# 30to50V-24V_10A.net
KiCad netlist of a schematic drawn in Altium Designer
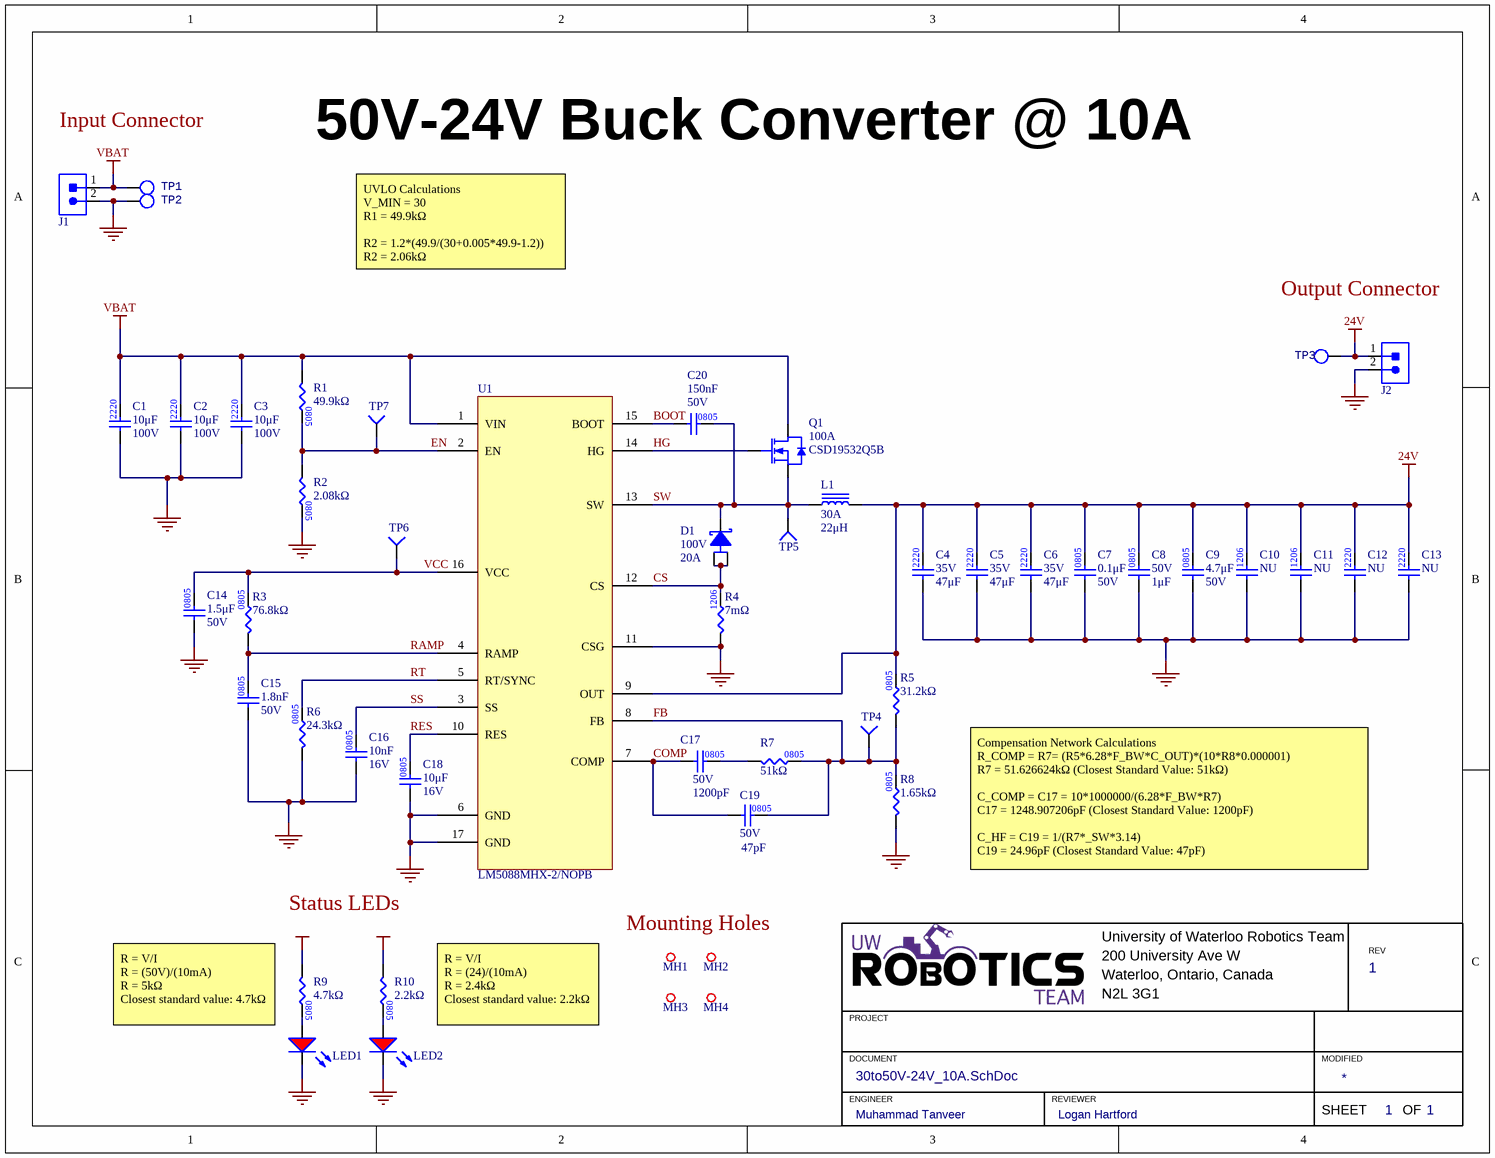
[diagram p0: 30to50V-24V_10A.SchDoc]

(export (version "E")
  (design (tool "Eeschema 10.0.6"))
  (components
    (comp (ref "C1")
      (value "10μF")
      (footprint "CAP2220")
      (description "CAP CER 10UF 100V X7S 2220")
      (fields (field (name "VOLTAGE RATING") "100V") (field (name "Comment") "CAP_10uF_50V_2220"))
      (libsource (lib "UWRT_Schematic_Library_2020") (part "CAP_10uF_50V_2220"))
    )
    (comp (ref "C2")
      (value "10μF")
      (footprint "CAP2220")
      (description "CAP CER 10UF 100V X7S 2220")
      (fields (field (name "VOLTAGE RATING") "100V") (field (name "Comment") "CAP_10uF_50V_2220"))
      (libsource (lib "UWRT_Schematic_Library_2020") (part "CAP_10uF_50V_2220"))
    )
    (comp (ref "C3")
      (value "10μF")
      (footprint "CAP2220")
      (description "CAP CER 10UF 100V X7S 2220")
      (fields (field (name "VOLTAGE RATING") "100V") (field (name "Comment") "CAP_10uF_50V_2220"))
      (libsource (lib "UWRT_Schematic_Library_2020") (part "CAP_10uF_50V_2220"))
    )
    (comp (ref "C4")
      (value "47μF")
      (footprint "CAP2220")
      (description "CAP CER 47UF 35V X7R 2220")
      (fields (field (name "VOLTAGE RATING") "35V") (field (name "Comment") "CAP_47uF_35V_2220"))
      (libsource (lib "UWRT_Schematic_Library_2020") (part "CAP_47uF_35V_2220"))
    )
    (comp (ref "C5")
      (value "47μF")
      (footprint "CAP2220")
      (description "CAP CER 47UF 35V X7R 2220")
      (fields (field (name "VOLTAGE RATING") "35V") (field (name "Comment") "CAP_47uF_35V_2220"))
      (libsource (lib "UWRT_Schematic_Library_2020") (part "CAP_47uF_35V_2220"))
    )
    (comp (ref "C6")
      (value "47μF")
      (footprint "CAP2220")
      (description "CAP CER 47UF 35V X7R 2220")
      (fields (field (name "VOLTAGE RATING") "35V") (field (name "Comment") "CAP_47uF_35V_2220"))
      (libsource (lib "UWRT_Schematic_Library_2020") (part "CAP_47uF_35V_2220"))
    )
    (comp (ref "C7")
      (value "0.1μF")
      (footprint "CAP0805")
      (description "CAP CER 0.1UF 50V X7R 0805")
      (fields
        (field (name "LCSC PART #") "C49678")
        (field (name "VOLTAGE RATING") "50V")
        (field (name "Comment") "CAP_0.1uF_50V_0805")
      )
      (libsource (lib "UWRT_Schematic_Library_2020") (part "CAP_0.1uF_50V_0805"))
    )
    (comp (ref "C8")
      (value "1μF")
      (footprint "CAP0805")
      (description "CAP CER 1UF 50V X7R 0805")
      (fields
        (field (name "LCSC PART #") "C28323")
        (field (name "VOLTAGE RATING") "50V")
        (field (name "Comment") "CAP_1uF_50V_0805")
      )
      (libsource (lib "UWRT_Schematic_Library_2020") (part "CAP_1uF_50V_0805"))
    )
    (comp (ref "C9")
      (value "4.7μF")
      (footprint "CAP0805")
      (description "CAP CER 4.7UF 50V X5R 0805")
      (fields
        (field (name "LCSC PART #") "C1779")
        (field (name "VOLTAGE RATING") "50V")
        (field (name "Comment") "CAP_4.7uF_50V_0805")
      )
      (libsource (lib "UWRT_Schematic_Library_2020") (part "CAP_4.7uF_50V_0805"))
    )
    (comp (ref "C10")
      (value "NU")
      (footprint "CAP1206")
      (description "PLACEHOLDER CAPACITOR")
      (fields (field (name "Comment") "CAP_NU_1206"))
      (libsource (lib "UWRT_Schematic_Library_2020") (part "CAP_NU_1206"))
    )
    (comp (ref "C11")
      (value "NU")
      (footprint "CAP1206")
      (description "PLACEHOLDER CAPACITOR")
      (fields (field (name "Comment") "CAP_NU_1206"))
      (libsource (lib "UWRT_Schematic_Library_2020") (part "CAP_NU_1206"))
    )
    (comp (ref "C12")
      (value "NU")
      (footprint "CAP2220")
      (description "PLACEHOLDER CAPACITOR")
      (fields (field (name "Comment") "CAP_NU_2220"))
      (libsource (lib "UWRT_Schematic_Library_2020") (part "CAP_NU_2220"))
    )
    (comp (ref "C13")
      (value "NU")
      (footprint "CAP2220")
      (description "PLACEHOLDER CAPACITOR")
      (fields (field (name "Comment") "CAP_NU_2220"))
      (libsource (lib "UWRT_Schematic_Library_2020") (part "CAP_NU_2220"))
    )
    (comp (ref "C14")
      (value "1.5μF")
      (footprint "CAP0805")
      (description "CAP CER 1.5UF 50V X7R 0805")
      (fields (field (name "VOLTAGE RATING") "50V") (field (name "Comment") "CAP_1.5uF_50V_0805"))
      (libsource (lib "UWRT_Schematic_Library_2020") (part "CAP_1.5uF_50V_0805"))
    )
    (comp (ref "C15")
      (value "1.8nF")
      (footprint "CAP0805")
      (description "CAP CER 1800PF 50V C0G/NP0 0805")
      (fields (field (name "VOLTAGE RATING") "50V") (field (name "Comment") "CAP_1.8nF_50V_0805"))
      (libsource (lib "UWRT_Schematic_Library_2020") (part "CAP_1.8nF_50V_0805"))
    )
    (comp (ref "C16")
      (value "10nF")
      (footprint "CAP0805")
      (description "CAP CER 10000PF 16V X7R 0805")
      (fields (field (name "VOLTAGE RATING") "16V") (field (name "Comment") "CAP_10nF_16V_0805"))
      (libsource (lib "UWRT_Schematic_Library_2020") (part "CAP_10nF_16V_0805"))
    )
    (comp (ref "C17")
      (value "1200pF")
      (footprint "CAP0805")
      (description "CAP CER 1200PF 50V X7R 0805")
      (fields (field (name "VOLTAGE RATING") "50V") (field (name "Comment") "CAP_1200pF_50V_0805"))
      (libsource (lib "UWRT_Schematic_Library_2020") (part "CAP_1200pF_50V_0805"))
    )
    (comp (ref "C18")
      (value "10μF")
      (footprint "CAP0805")
      (description "CAP CER 10UF 16V X5R 0805")
      (fields (field (name "VOLTAGE RATING") "16V") (field (name "Comment") "CAP_10uF_16V_0805"))
      (libsource (lib "UWRT_Schematic_Library_2020") (part "CAP_10uF_16V_0805"))
    )
    (comp (ref "C19")
      (value "47pF")
      (footprint "CAP0805")
      (description "CAP CER 47PF 50V C0G/NPO 0805")
      (fields (field (name "VOLTAGE RATING") "50V") (field (name "Comment") "CAP_47pF_50V_0805"))
      (libsource (lib "UWRT_Schematic_Library_2020") (part "CAP_47pF_50V_0805"))
    )
    (comp (ref "C20")
      (value "150nF")
      (footprint "CAP0805")
      (description "CAP CER 0.15UF 50V X7R 0805")
      (fields (field (name "VOLTAGE RATING") "50V") (field (name "Comment") "CAP_150nF_50V_0805"))
      (libsource (lib "UWRT_Schematic_Library_2020") (part "CAP_150nF_50V_0805"))
    )
    (comp (ref "D1")
      (value "DIO_SCHOTTKY_100V_20A")
      (footprint "D2PAK (TO-263AB) - STPS20M100SG-TR")
      (description "DIODE SCHOTTKY 100V 20A D2PAK")
      (fields (field (name "VR (MAX)") "100V") (field (name "FORWARD CURRENT") "20A"))
      (libsource (lib "UWRT_Schematic_Library_2020") (part "DIO_SCHOTTKY_100V_20A"))
    )
    (comp (ref "J1")
      (value "CON_2POS_SCREW_TERM")
      (footprint "1935161")
      (description "TERM BLK 2POS SIDE ENTRY 5MM")
      (libsource (lib "UWRT_Schematic_Library_2020") (part "CON_2POS_SCREW_TERM"))
    )
    (comp (ref "J2")
      (value "CON_2POS_SCREW_TERM")
      (footprint "1935161")
      (description "TERM BLK 2POS SIDE ENTRY 5MM")
      (libsource (lib "") (part "CON_2POS_SCREW_TERM_1"))
    )
    (comp (ref "L1")
      (value "IND_22uH_30A")
      (footprint "7443642200")
      (description "FIXED IND 22UH 30A 2.4 MOHM SMD")
      (fields (field (name "CURRENT RATING") "30A") (field (name "INDUCTANCE") "22μH"))
      (libsource (lib "UWRT_Schematic_Library_2020") (part "IND_22uH_30A"))
    )
    (comp (ref "LED1")
      (value "LED_RED")
      (footprint "LED_0805_RED")
      (description "LED RED DIFFUSED 0805 SMD")
      (libsource (lib "UWRT_Schematic_Library_2020") (part "LED_RED"))
    )
    (comp (ref "LED2")
      (value "LED_RED")
      (footprint "LED_0805_RED")
      (description "LED RED DIFFUSED 0805 SMD")
      (libsource (lib "UWRT_Schematic_Library_2020") (part "LED_RED"))
    )
    (comp (ref "MH1")
      (value "MOUNTING_HOLE_M3_GIMBAL_REV2")
      (footprint "MOUNTING_HOLE_3mm_GIMBAL_REV2")
      (description "MOUNTING_HOLE_M3 Gimbal Rev2")
      (libsource (lib "UWRT_Schematic_Library_2020") (part "MOUNTING_HOLE_M3_GIMBAL_REV2"))
    )
    (comp (ref "MH2")
      (value "MOUNTING_HOLE_M3_GIMBAL_REV2")
      (footprint "MOUNTING_HOLE_3mm_GIMBAL_REV2")
      (description "MOUNTING_HOLE_M3 Gimbal Rev2")
      (libsource (lib "UWRT_Schematic_Library_2020") (part "MOUNTING_HOLE_M3_GIMBAL_REV2"))
    )
    (comp (ref "MH3")
      (value "MOUNTING_HOLE_M3_GIMBAL_REV2")
      (footprint "MOUNTING_HOLE_3mm_GIMBAL_REV2")
      (description "MOUNTING_HOLE_M3 Gimbal Rev2")
      (libsource (lib "UWRT_Schematic_Library_2020") (part "MOUNTING_HOLE_M3_GIMBAL_REV2"))
    )
    (comp (ref "MH4")
      (value "MOUNTING_HOLE_M3_GIMBAL_REV2")
      (footprint "MOUNTING_HOLE_3mm_GIMBAL_REV2")
      (description "MOUNTING_HOLE_M3 Gimbal Rev2")
      (libsource (lib "UWRT_Schematic_Library_2020") (part "MOUNTING_HOLE_M3_GIMBAL_REV2"))
    )
    (comp (ref "Q1")
      (value "NMOS_100V_100A")
      (footprint "8-VSON")
      (description "MOSFET N-CH 100V 100A 8VSON")
      (fields (field (name "ID") "100A") (field (name "MANUFACTURER PART NUMBER 1") "CSD19532Q5B"))
      (libsource (lib "UWRT_Schematic_Library_2020") (part "NMOS_100V_100A"))
    )
    (comp (ref "R1")
      (value "49.9kΩ")
      (footprint "RES0805")
      (description "RES 49.9K OHM 1% 1/8W 0805")
      (fields (field (name "LCSC PART #") "C17719") (field (name "Comment") "RES_49.9kΩ_0805_1%"))
      (libsource (lib "UWRT_Schematic_Library_2020") (part "RES_49.9kΩ_0805_1%"))
    )
    (comp (ref "R2")
      (value "2.08kΩ")
      (footprint "RES0805")
      (description "RES 2.08K OHM 0.05% 1/8W 0805")
      (fields (field (name "Comment") "RES_2.08kΩ_0805_0.05%"))
      (libsource (lib "UWRT_Schematic_Library_2020") (part "RES_2.08kΩ_0805_0.05%"))
    )
    (comp (ref "R3")
      (value "76.8kΩ")
      (footprint "RES0805")
      (description "RES 76.8K OHM 1% 1/8W 0805")
      (fields (field (name "Comment") "RES_76.8kΩ_0805_1%"))
      (libsource (lib "UWRT_Schematic_Library_2020") (part "RES_76.8kΩ_0805_1%"))
    )
    (comp (ref "R4")
      (value "7mΩ")
      (footprint "RES1206")
      (description "RES 0.007 OHM 1% 1W 1206")
      (fields (field (name "Comment") "RES_0.007Ω_1206_1%"))
      (libsource (lib "UWRT_Schematic_Library_2020") (part "RES_0.007Ω_1206_1%"))
    )
    (comp (ref "R5")
      (value "31.2kΩ")
      (footprint "RES0805")
      (description "RES 31.2K OHM 0.1% 1/8W 0805")
      (fields (field (name "Comment") "RES_31.2KΩ_0805_0.1%"))
      (libsource (lib "UWRT_Schematic_Library_2020") (part "RES_31.2KΩ_0805_0.1%"))
    )
    (comp (ref "R6")
      (value "24.3kΩ")
      (footprint "RES0805")
      (description "RES 24.3K OHM 1% 1/8W 0805")
      (fields (field (name "POWER") "0.125W") (field (name "TOLERANCE") "1%"))
      (libsource (lib "UWRT_Schematic_Library_2020") (part "RES_24.3kΩ_0805_1%"))
    )
    (comp (ref "R7")
      (value "51kΩ")
      (footprint "RES0805")
      (description "RES 51K OHM 1% 1/8W 0805")
      (fields (field (name "Comment") "RES_51kΩ_0805_5%"))
      (libsource (lib "UWRT_Schematic_Library_2020") (part "RES_51kΩ_0805_5%"))
    )
    (comp (ref "R8")
      (value "1.65kΩ")
      (footprint "RES0805")
      (description "RES 1.65K OHM 0.1% 1/4W 0805")
      (fields (field (name "Comment") "RES_1.65KΩ_0805_0.1%"))
      (libsource (lib "UWRT_Schematic_Library_2020") (part "RES_1.65KΩ_0805_0.1%"))
    )
    (comp (ref "R9")
      (value "4.7kΩ")
      (footprint "RES0805")
      (description "RES 4.7K OHM 5% 1/8W 0805")
      (fields (field (name "LCSC PART #") "C17673") (field (name "Comment") "RES_4.7kΩ_0805_5%"))
      (libsource (lib "UWRT_Schematic_Library_2020") (part "RES_4.7kΩ_0805_5%"))
    )
    (comp (ref "R10")
      (value "2.2kΩ")
      (footprint "RES0805")
      (description "RES 2.2K OHM 5% 1/8W 0805")
      (fields (field (name "TOLERANCE") "5%") (field (name "Comment") "RES_2.2kΩ_0805_5%"))
      (libsource (lib "UWRT_Schematic_Library_2020") (part "RES_2.2kΩ_0805_5%"))
    )
    (comp (ref "TP1")
      (value "TESTPOINT_LOOP")
      (footprint "TESTPOINT_LOOP")
      (description "TESTPOINT THRUHOLE")
      (libsource (lib "UWRT_Schematic_Library_2020") (part "TESTPOINT_LOOP"))
    )
    (comp (ref "TP2")
      (value "TESTPOINT_LOOP")
      (footprint "TESTPOINT_LOOP")
      (description "TESTPOINT THRUHOLE")
      (libsource (lib "UWRT_Schematic_Library_2020") (part "TESTPOINT_LOOP"))
    )
    (comp (ref "TP3")
      (value "TESTPOINT_LOOP")
      (footprint "TESTPOINT_LOOP")
      (description "TESTPOINT THRUHOLE")
      (libsource (lib "UWRT_Schematic_Library_2020") (part "TESTPOINT_LOOP"))
    )
    (comp (ref "TP4")
      (value "TESTPOINT_1MM_CIRCLE")
      (footprint "TESTPOINT_CIRCLE_1MM")
      (description "TESTPOINT 1MM CIRCLE")
      (libsource (lib "UWRT_Schematic_Library_2020") (part "TESTPOINT_1MM_CIRCLE"))
    )
    (comp (ref "TP5")
      (value "TESTPOINT_1MM_CIRCLE")
      (footprint "TESTPOINT_CIRCLE_1MM")
      (description "TESTPOINT 1MM CIRCLE")
      (libsource (lib "UWRT_Schematic_Library_2020") (part "TESTPOINT_1MM_CIRCLE"))
    )
    (comp (ref "TP6")
      (value "TESTPOINT_1MM_CIRCLE")
      (footprint "TESTPOINT_CIRCLE_1MM")
      (description "TESTPOINT 1MM CIRCLE")
      (libsource (lib "UWRT_Schematic_Library_2020") (part "TESTPOINT_1MM_CIRCLE"))
    )
    (comp (ref "TP7")
      (value "TESTPOINT_1MM_CIRCLE")
      (footprint "TESTPOINT_CIRCLE_1MM")
      (description "TESTPOINT 1MM CIRCLE")
      (libsource (lib "UWRT_Schematic_Library_2020") (part "TESTPOINT_1MM_CIRCLE"))
    )
    (comp (ref "U1")
      (value "LM5088")
      (footprint "LM5088")
      (description "IC REG CTRLR BUCK 16HTSSOP")
      (fields (field (name "MANUFACTURER PART NUMBER 1") "LM5088MHX-2/NOPB"))
      (libsource (lib "UWRT_Schematic_Library_2020") (part "LM5088MHX-2/NOPB"))
    )
  )
  (nets
    (net (code "1") (name "/BOOT") (class "Default")
      (node (ref "C20") (pin "1") (pinfunction "1_1") (pintype "passive"))
      (node (ref "U1") (pin "15") (pinfunction "BOOT_15") (pintype "passive"))
    )
    (net (code "2") (name "/COMP") (class "Default")
      (node (ref "C17") (pin "1") (pinfunction "1_1") (pintype "passive"))
      (node (ref "C19") (pin "1") (pinfunction "1_1") (pintype "passive"))
      (node (ref "U1") (pin "7") (pinfunction "COMP_7") (pintype "passive"))
    )
    (net (code "3") (name "/CS") (class "Default")
      (node (ref "D1") (pin "1") (pinfunction "Anode_1") (pintype "passive"))
      (node (ref "D1") (pin "2") (pinfunction "Anode_2") (pintype "passive"))
      (node (ref "R4") (pin "2") (pinfunction "2_2") (pintype "passive"))
      (node (ref "U1") (pin "12") (pinfunction "CS_12") (pintype "passive"))
    )
    (net (code "4") (name "/EN") (class "Default")
      (node (ref "R1") (pin "2") (pinfunction "2_2") (pintype "passive"))
      (node (ref "R2") (pin "1") (pinfunction "1_1") (pintype "passive"))
      (node (ref "TP7") (pin "1") (pinfunction "=value_1") (pintype "passive"))
      (node (ref "U1") (pin "2") (pinfunction "EN_2") (pintype "passive"))
    )
    (net (code "5") (name "/FB") (class "Default")
      (node (ref "C19") (pin "2") (pinfunction "2_2") (pintype "passive"))
      (node (ref "R5") (pin "1") (pinfunction "1_1") (pintype "passive"))
      (node (ref "R7") (pin "2") (pinfunction "2_2") (pintype "passive"))
      (node (ref "R8") (pin "2") (pinfunction "2_2") (pintype "passive"))
      (node (ref "TP4") (pin "1") (pinfunction "=value_1") (pintype "passive"))
      (node (ref "U1") (pin "8") (pinfunction "FB_8") (pintype "passive"))
    )
    (net (code "6") (name "/HG") (class "Default")
      (node (ref "Q1") (pin "1") (pinfunction "Gate_1") (pintype "passive"))
      (node (ref "U1") (pin "14") (pinfunction "HG_14") (pintype "passive"))
    )
    (net (code "7") (name "/RAMP") (class "Default")
      (node (ref "C15") (pin "2") (pinfunction "2_2") (pintype "passive"))
      (node (ref "R3") (pin "1") (pinfunction "1_1") (pintype "passive"))
      (node (ref "U1") (pin "4") (pinfunction "RAMP_4") (pintype "passive"))
    )
    (net (code "8") (name "/RES") (class "Default")
      (node (ref "C18") (pin "2") (pinfunction "2_2") (pintype "passive"))
      (node (ref "U1") (pin "10") (pinfunction "RES_10") (pintype "passive"))
    )
    (net (code "9") (name "/RT") (class "Default")
      (node (ref "R6") (pin "2") (pinfunction "2_2") (pintype "passive"))
      (node (ref "U1") (pin "5") (pinfunction "RT/SYNC_5") (pintype "passive"))
    )
    (net (code "10") (name "/SS") (class "Default")
      (node (ref "C16") (pin "2") (pinfunction "2_2") (pintype "passive"))
      (node (ref "U1") (pin "3") (pinfunction "SS_3") (pintype "passive"))
    )
    (net (code "11") (name "/SW") (class "Default")
      (node (ref "C20") (pin "2") (pinfunction "2_2") (pintype "passive"))
      (node (ref "D1") (pin "3") (pinfunction "Cathode_3") (pintype "passive"))
      (node (ref "L1") (pin "1") (pinfunction "1_1") (pintype "passive"))
      (node (ref "Q1") (pin "2") (pinfunction "Source_2") (pintype "passive"))
      (node (ref "TP5") (pin "1") (pinfunction "=value_1") (pintype "passive"))
      (node (ref "U1") (pin "13") (pinfunction "SW_13") (pintype "passive"))
    )
    (net (code "12") (name "/VCC") (class "Default")
      (node (ref "C14") (pin "2") (pinfunction "2_2") (pintype "passive"))
      (node (ref "R3") (pin "2") (pinfunction "2_2") (pintype "passive"))
      (node (ref "TP6") (pin "1") (pinfunction "=value_1") (pintype "passive"))
      (node (ref "U1") (pin "16") (pinfunction "VCC_16") (pintype "passive"))
    )
    (net (code "13") (name "24V") (class "Default")
      (node (ref "C10") (pin "2") (pinfunction "2_2") (pintype "passive"))
      (node (ref "C11") (pin "2") (pinfunction "2_2") (pintype "passive"))
      (node (ref "C12") (pin "2") (pinfunction "2_2") (pintype "passive"))
      (node (ref "C13") (pin "2") (pinfunction "2_2") (pintype "passive"))
      (node (ref "C4") (pin "2") (pinfunction "2_2") (pintype "passive"))
      (node (ref "C5") (pin "2") (pinfunction "2_2") (pintype "passive"))
      (node (ref "C6") (pin "2") (pinfunction "2_2") (pintype "passive"))
      (node (ref "C7") (pin "2") (pinfunction "2_2") (pintype "passive"))
      (node (ref "C8") (pin "2") (pinfunction "2_2") (pintype "passive"))
      (node (ref "C9") (pin "2") (pinfunction "2_2") (pintype "passive"))
      (node (ref "J2") (pin "1") (pinfunction "1_1") (pintype "passive"))
      (node (ref "L1") (pin "2") (pinfunction "2_2") (pintype "passive"))
      (node (ref "R10") (pin "1") (pinfunction "1_1") (pintype "passive"))
      (node (ref "R5") (pin "2") (pinfunction "2_2") (pintype "passive"))
      (node (ref "TP3") (pin "1") (pintype "passive"))
      (node (ref "U1") (pin "9") (pinfunction "OUT_9") (pintype "passive"))
    )
    (net (code "14") (name "GND") (class "Default")
      (node (ref "C1") (pin "1") (pinfunction "1_1") (pintype "passive"))
      (node (ref "C10") (pin "1") (pinfunction "1_1") (pintype "passive"))
      (node (ref "C11") (pin "1") (pinfunction "1_1") (pintype "passive"))
      (node (ref "C12") (pin "1") (pinfunction "1_1") (pintype "passive"))
      (node (ref "C13") (pin "1") (pinfunction "1_1") (pintype "passive"))
      (node (ref "C14") (pin "1") (pinfunction "1_1") (pintype "passive"))
      (node (ref "C15") (pin "1") (pinfunction "1_1") (pintype "passive"))
      (node (ref "C16") (pin "1") (pinfunction "1_1") (pintype "passive"))
      (node (ref "C18") (pin "1") (pinfunction "1_1") (pintype "passive"))
      (node (ref "C2") (pin "1") (pinfunction "1_1") (pintype "passive"))
      (node (ref "C3") (pin "1") (pinfunction "1_1") (pintype "passive"))
      (node (ref "C4") (pin "1") (pinfunction "1_1") (pintype "passive"))
      (node (ref "C5") (pin "1") (pinfunction "1_1") (pintype "passive"))
      (node (ref "C6") (pin "1") (pinfunction "1_1") (pintype "passive"))
      (node (ref "C7") (pin "1") (pinfunction "1_1") (pintype "passive"))
      (node (ref "C8") (pin "1") (pinfunction "1_1") (pintype "passive"))
      (node (ref "C9") (pin "1") (pinfunction "1_1") (pintype "passive"))
      (node (ref "J1") (pin "2") (pinfunction "2_2") (pintype "passive"))
      (node (ref "J2") (pin "2") (pinfunction "2_2") (pintype "passive"))
      (node (ref "LED1") (pin "2") (pinfunction "K_2") (pintype "passive"))
      (node (ref "LED2") (pin "2") (pinfunction "K_2") (pintype "passive"))
      (node (ref "R2") (pin "2") (pinfunction "2_2") (pintype "passive"))
      (node (ref "R4") (pin "1") (pinfunction "1_1") (pintype "passive"))
      (node (ref "R6") (pin "1") (pinfunction "1_1") (pintype "passive"))
      (node (ref "R8") (pin "1") (pinfunction "1_1") (pintype "passive"))
      (node (ref "TP2") (pin "1") (pintype "passive"))
      (node (ref "U1") (pin "11") (pinfunction "CSG_11") (pintype "passive"))
      (node (ref "U1") (pin "17") (pinfunction "GND_17") (pintype "passive"))
      (node (ref "U1") (pin "6") (pinfunction "GND_6") (pintype "passive"))
    )
    (net (code "15") (name "Net-(C17-Pad2)") (class "Default")
      (node (ref "C17") (pin "2") (pinfunction "2_2") (pintype "passive"))
      (node (ref "R7") (pin "1") (pinfunction "1_1") (pintype "passive"))
    )
    (net (code "16") (name "Net-(LED1-A)") (class "Default")
      (node (ref "LED1") (pin "1") (pinfunction "A_1") (pintype "passive"))
      (node (ref "R9") (pin "2") (pinfunction "2_2") (pintype "passive"))
    )
    (net (code "17") (name "Net-(LED2-A)") (class "Default")
      (node (ref "LED2") (pin "1") (pinfunction "A_1") (pintype "passive"))
      (node (ref "R10") (pin "2") (pinfunction "2_2") (pintype "passive"))
    )
    (net (code "18") (name "VBAT") (class "Default")
      (node (ref "C1") (pin "2") (pinfunction "2_2") (pintype "passive"))
      (node (ref "C2") (pin "2") (pinfunction "2_2") (pintype "passive"))
      (node (ref "C3") (pin "2") (pinfunction "2_2") (pintype "passive"))
      (node (ref "J1") (pin "1") (pinfunction "1_1") (pintype "passive"))
      (node (ref "Q1") (pin "3") (pinfunction "Drain_3") (pintype "passive"))
      (node (ref "R1") (pin "1") (pinfunction "1_1") (pintype "passive"))
      (node (ref "R9") (pin "1") (pinfunction "1_1") (pintype "passive"))
      (node (ref "TP1") (pin "1") (pintype "passive"))
      (node (ref "U1") (pin "1") (pinfunction "VIN_1") (pintype "passive"))
    )
  )
)
